# DMXDebugger.net
KiCad netlist of a schematic drawn in EAGLE
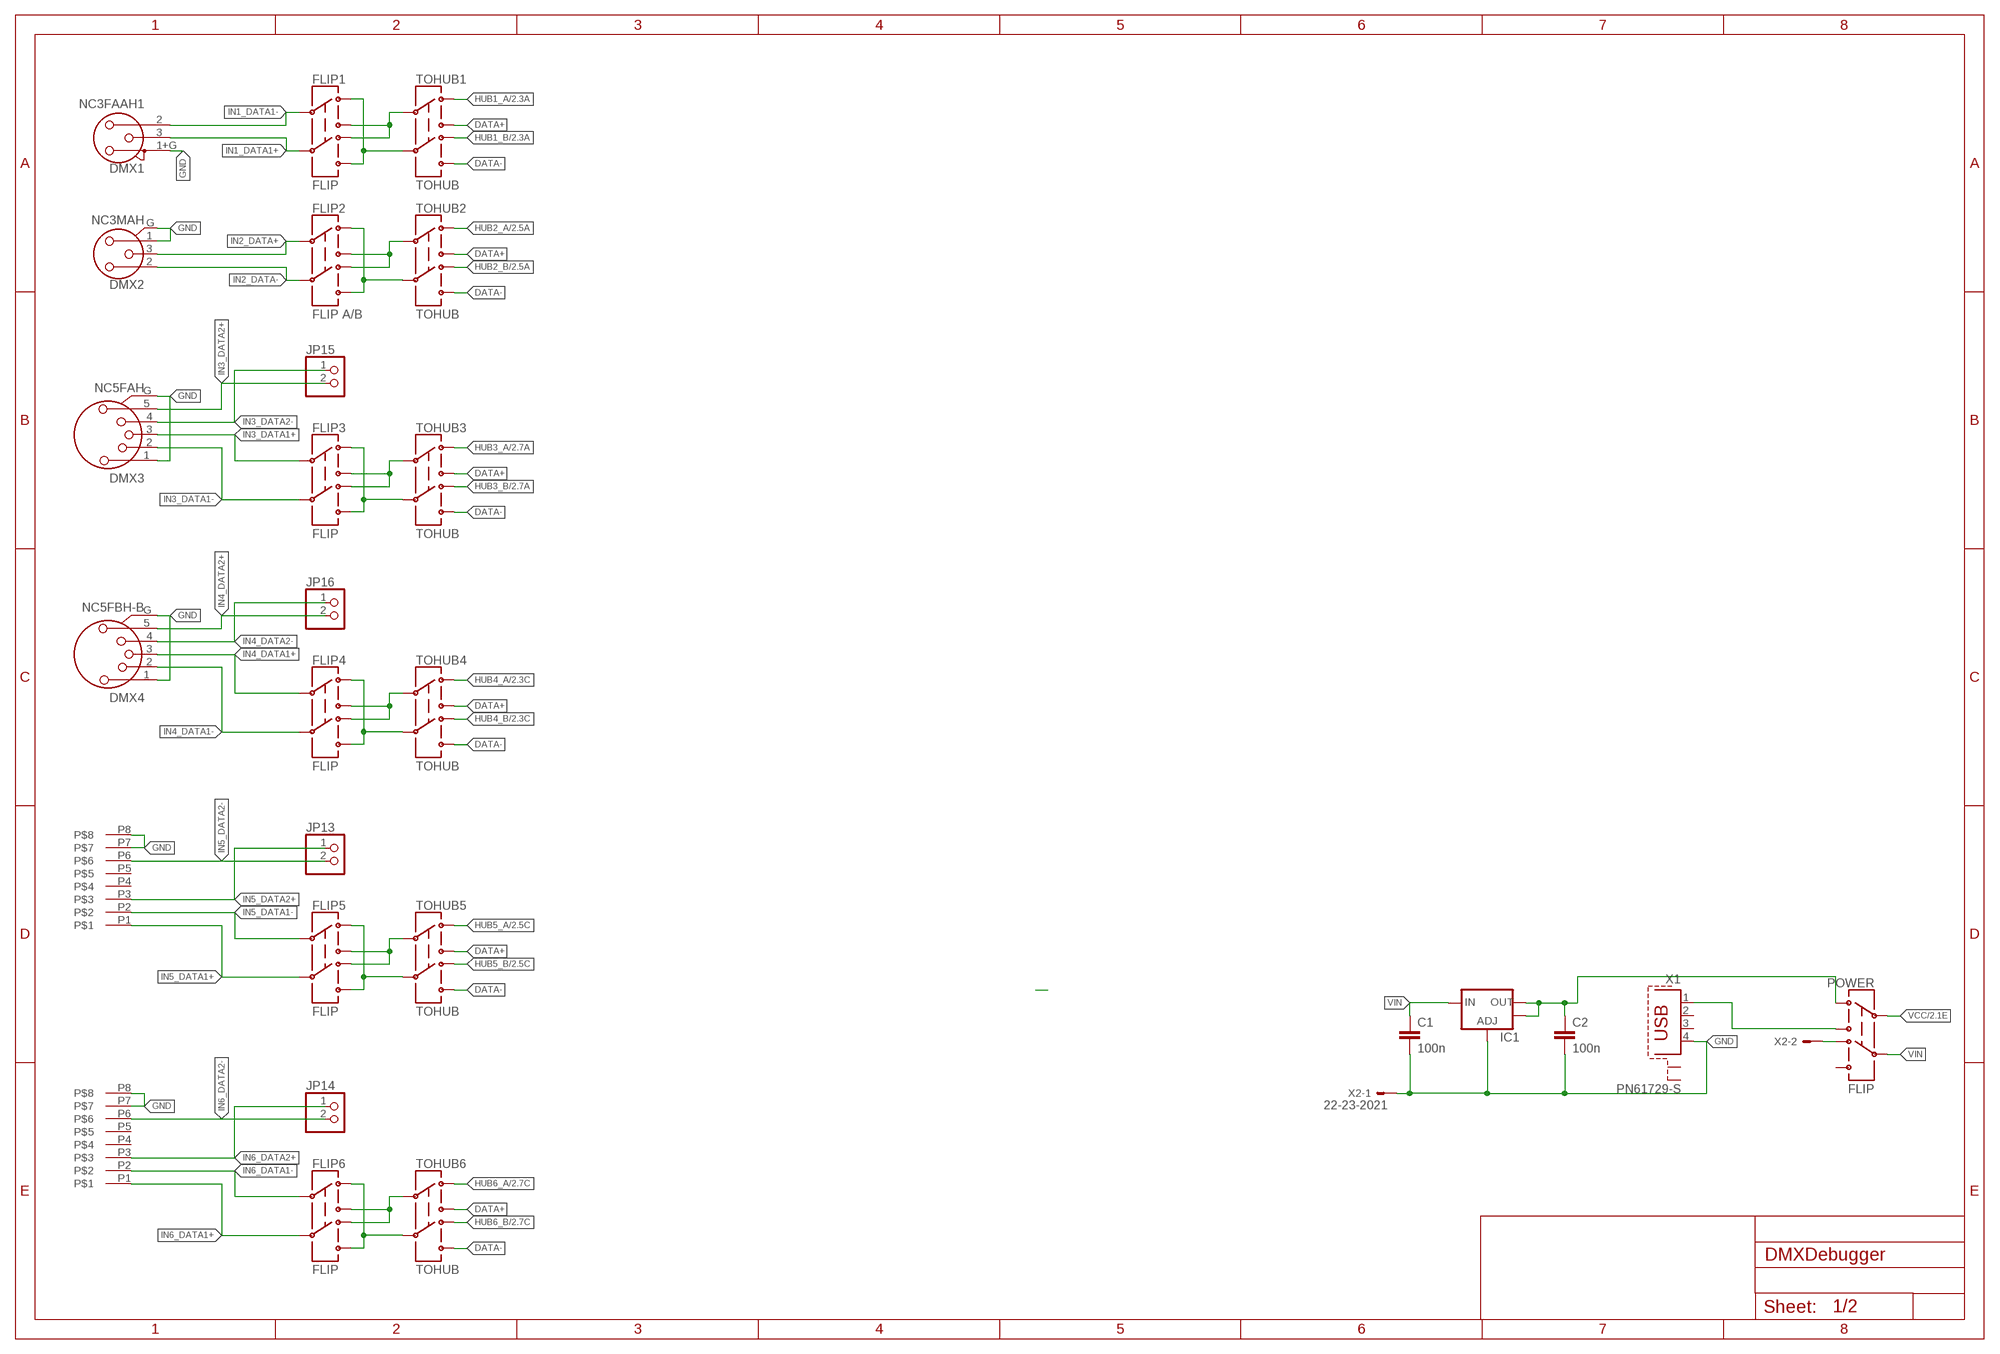
[diagram p0: schematic, sheet 1]
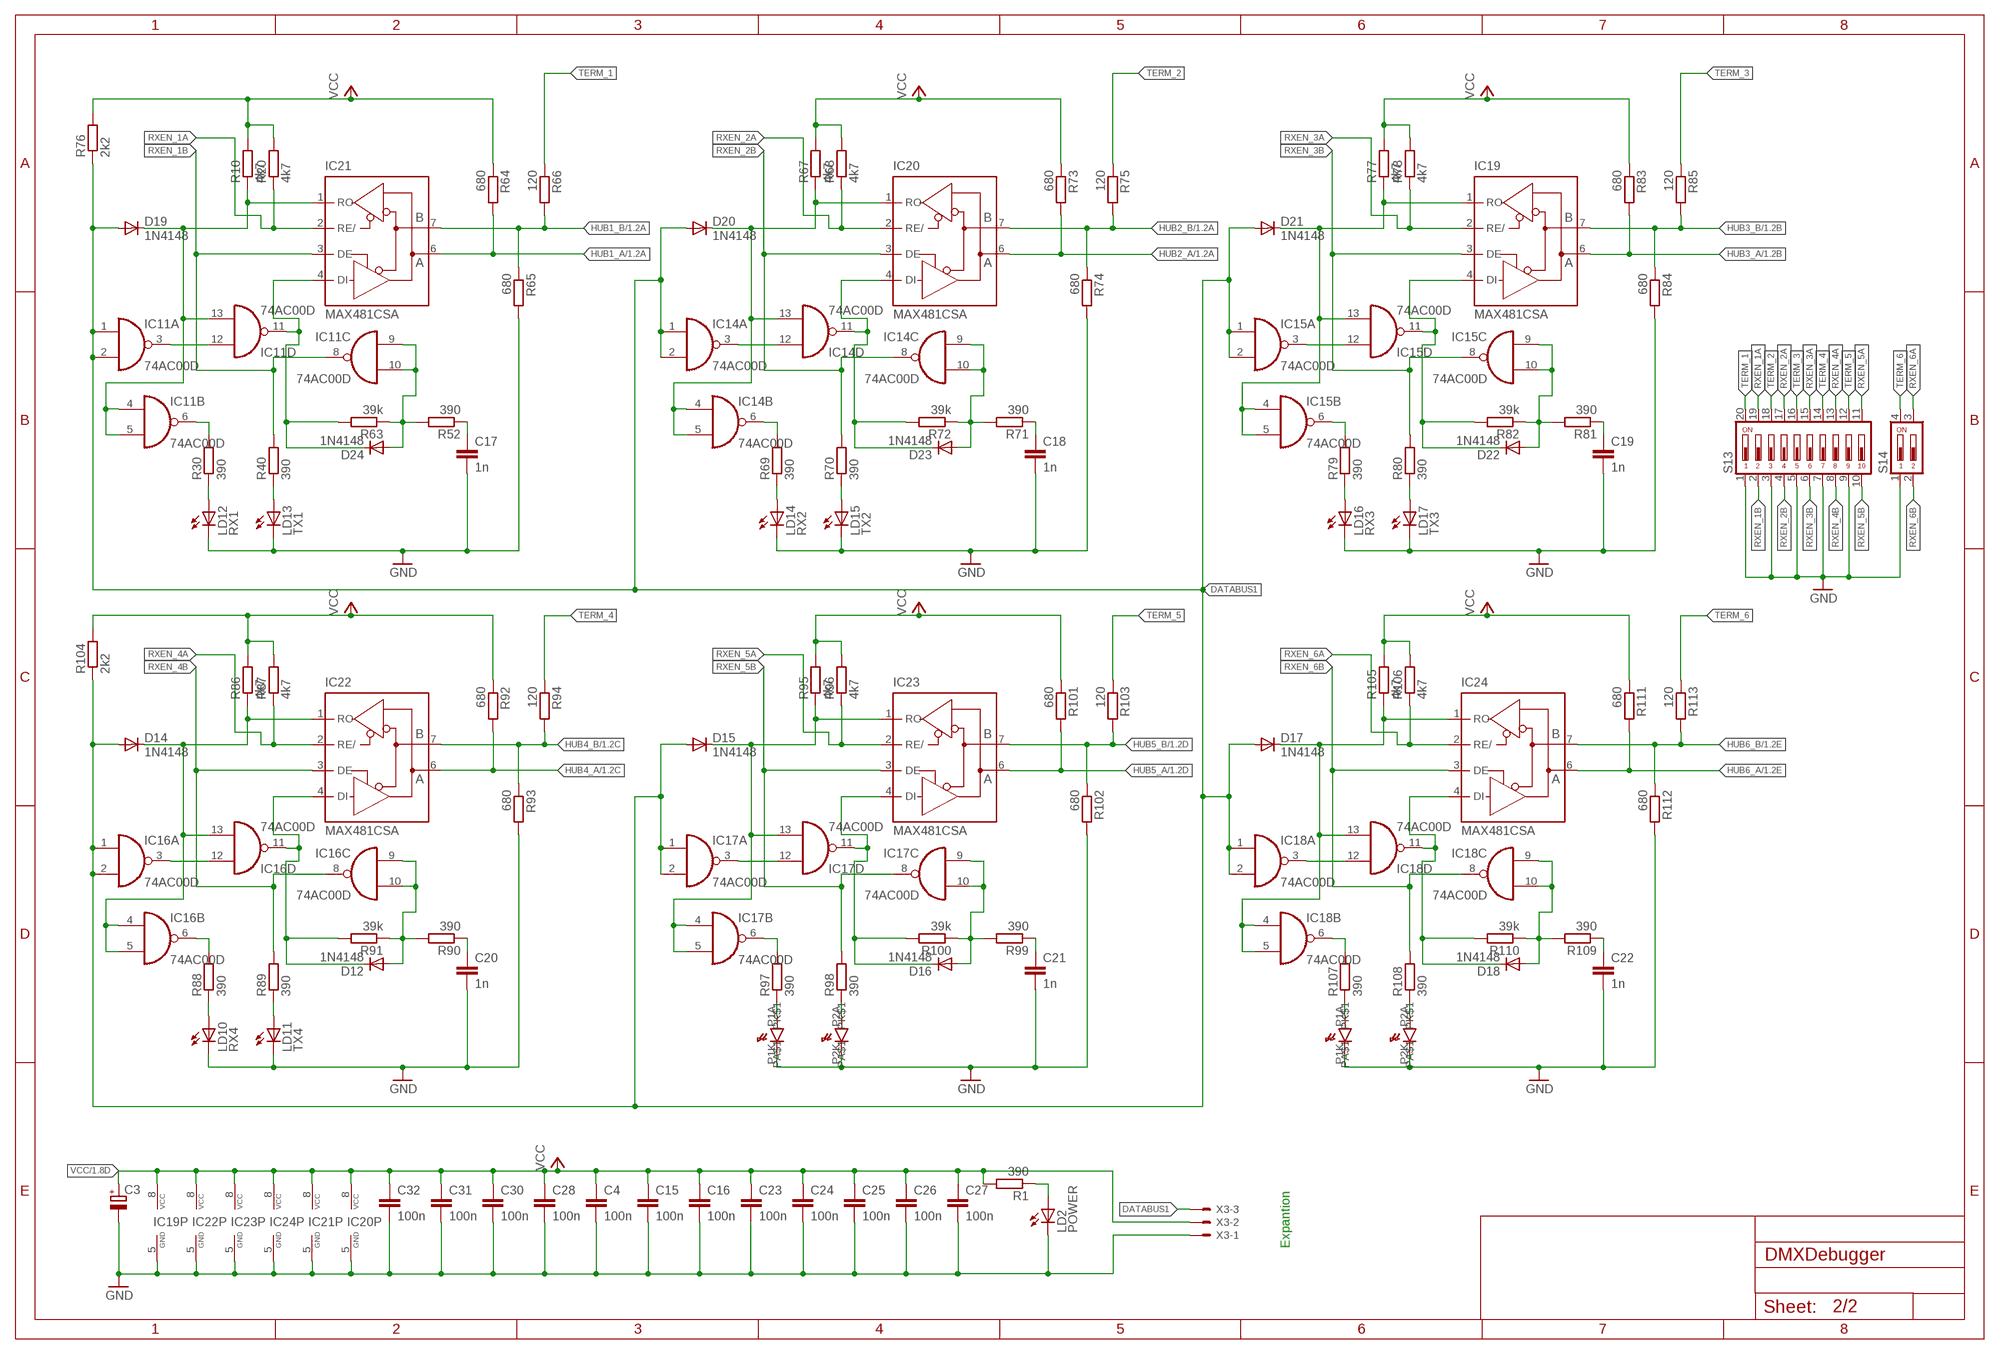
[diagram p1: schematic, sheet 2]

(export (version "E")
  (design (tool "Eeschema 10.0.6"))
  (components
    (comp (ref "C3")
      (value "CPOL-EUD")
      (footprint "eagle-import:PANASONIC_D")
      (libsource (lib "eagle-import") (part "CPOL-EUD"))
    )
    (comp (ref "C4")
      (value "100n")
      (footprint "eagle-import:C1206")
      (libsource (lib "eagle-import") (part "C-EUC1206"))
    )
    (comp (ref "C15")
      (value "100n")
      (footprint "eagle-import:C1206")
      (libsource (lib "eagle-import") (part "C-EUC1206"))
    )
    (comp (ref "C16")
      (value "100n")
      (footprint "eagle-import:C1206")
      (libsource (lib "eagle-import") (part "C-EUC1206"))
    )
    (comp (ref "C17")
      (value "1n")
      (footprint "eagle-import:C1206")
      (libsource (lib "eagle-import") (part "C-EUC1206"))
    )
    (comp (ref "C18")
      (value "1n")
      (footprint "eagle-import:C1206")
      (libsource (lib "eagle-import") (part "C-EUC1206"))
    )
    (comp (ref "C19")
      (value "1n")
      (footprint "eagle-import:C1206")
      (libsource (lib "eagle-import") (part "C-EUC1206"))
    )
    (comp (ref "C20")
      (value "1n")
      (footprint "eagle-import:C1206")
      (libsource (lib "eagle-import") (part "C-EUC1206"))
    )
    (comp (ref "C21")
      (value "1n")
      (footprint "eagle-import:C1206")
      (libsource (lib "eagle-import") (part "C-EUC1206"))
    )
    (comp (ref "C22")
      (value "1n")
      (footprint "eagle-import:C1206")
      (libsource (lib "eagle-import") (part "C-EUC1206"))
    )
    (comp (ref "C23")
      (value "100n")
      (footprint "eagle-import:C1206")
      (libsource (lib "eagle-import") (part "C-EUC1206"))
    )
    (comp (ref "C24")
      (value "100n")
      (footprint "eagle-import:C1206")
      (libsource (lib "eagle-import") (part "C-EUC1206"))
    )
    (comp (ref "C25")
      (value "100n")
      (footprint "eagle-import:C1206")
      (libsource (lib "eagle-import") (part "C-EUC1206"))
    )
    (comp (ref "C26")
      (value "100n")
      (footprint "eagle-import:C1206")
      (libsource (lib "eagle-import") (part "C-EUC1206"))
    )
    (comp (ref "C27")
      (value "100n")
      (footprint "eagle-import:C1206")
      (libsource (lib "eagle-import") (part "C-EUC1206"))
    )
    (comp (ref "C28")
      (value "100n")
      (footprint "eagle-import:C1206")
      (libsource (lib "eagle-import") (part "C-EUC1206"))
    )
    (comp (ref "C30")
      (value "100n")
      (footprint "eagle-import:C1206")
      (libsource (lib "eagle-import") (part "C-EUC1206"))
    )
    (comp (ref "C31")
      (value "100n")
      (footprint "eagle-import:C1206")
      (libsource (lib "eagle-import") (part "C-EUC1206"))
    )
    (comp (ref "C32")
      (value "100n")
      (footprint "eagle-import:C1206")
      (libsource (lib "eagle-import") (part "C-EUC1206"))
    )
    (comp (ref "D12")
      (value "1N4148")
      (footprint "eagle-import:MINIMELF")
      (libsource (lib "eagle-import") (part "DIODE-MINIMELF"))
    )
    (comp (ref "D14")
      (value "1N4148")
      (footprint "eagle-import:MINIMELF")
      (libsource (lib "eagle-import") (part "DIODE-MINIMELF"))
    )
    (comp (ref "D15")
      (value "1N4148")
      (footprint "eagle-import:MINIMELF")
      (libsource (lib "eagle-import") (part "DIODE-MINIMELF"))
    )
    (comp (ref "D16")
      (value "1N4148")
      (footprint "eagle-import:MINIMELF")
      (libsource (lib "eagle-import") (part "DIODE-MINIMELF"))
    )
    (comp (ref "D17")
      (value "1N4148")
      (footprint "eagle-import:MINIMELF")
      (libsource (lib "eagle-import") (part "DIODE-MINIMELF"))
    )
    (comp (ref "D18")
      (value "1N4148")
      (footprint "eagle-import:MINIMELF")
      (libsource (lib "eagle-import") (part "DIODE-MINIMELF"))
    )
    (comp (ref "D19")
      (value "1N4148")
      (footprint "eagle-import:MINIMELF")
      (libsource (lib "eagle-import") (part "DIODE-MINIMELF"))
    )
    (comp (ref "D20")
      (value "1N4148")
      (footprint "eagle-import:MINIMELF")
      (libsource (lib "eagle-import") (part "DIODE-MINIMELF"))
    )
    (comp (ref "D21")
      (value "1N4148")
      (footprint "eagle-import:MINIMELF")
      (libsource (lib "eagle-import") (part "DIODE-MINIMELF"))
    )
    (comp (ref "D22")
      (value "1N4148")
      (footprint "eagle-import:MINIMELF")
      (libsource (lib "eagle-import") (part "DIODE-MINIMELF"))
    )
    (comp (ref "D23")
      (value "1N4148")
      (footprint "eagle-import:MINIMELF")
      (libsource (lib "eagle-import") (part "DIODE-MINIMELF"))
    )
    (comp (ref "D24")
      (value "1N4148")
      (footprint "eagle-import:MINIMELF")
      (libsource (lib "eagle-import") (part "DIODE-MINIMELF"))
    )
    (comp (ref "DMX5")
      (value "RJHS508")
      (footprint "eagle-import:P-RJHS-538X")
      (libsource (lib "eagle-import") (part "RJHS508"))
    )
    (comp (ref "DMX6")
      (value "RJHS508")
      (footprint "eagle-import:P-RJHS-538X")
      (libsource (lib "eagle-import") (part "RJHS508"))
    )
    (comp (ref "IC11")
      (value "74AC00D")
      (footprint "eagle-import:SO14")
      (libsource (lib "eagle-import") (part "7400DAC"))
    )
    (comp (ref "IC14")
      (value "74AC00D")
      (footprint "eagle-import:SO14")
      (libsource (lib "eagle-import") (part "7400DAC"))
    )
    (comp (ref "IC15")
      (value "74AC00D")
      (footprint "eagle-import:SO14")
      (libsource (lib "eagle-import") (part "7400DAC"))
    )
    (comp (ref "IC16")
      (value "74AC00D")
      (footprint "eagle-import:SO14")
      (libsource (lib "eagle-import") (part "7400DAC"))
    )
    (comp (ref "IC17")
      (value "74AC00D")
      (footprint "eagle-import:SO14")
      (libsource (lib "eagle-import") (part "7400DAC"))
    )
    (comp (ref "IC18")
      (value "74AC00D")
      (footprint "eagle-import:SO14")
      (libsource (lib "eagle-import") (part "7400DAC"))
    )
    (comp (ref "IC19")
      (value "MAX481CSA")
      (footprint "eagle-import:SO08")
      (fields (field (name "MF") "MAXIM"))
      (libsource (lib "eagle-import") (part "MAX481CSA"))
    )
    (comp (ref "IC20")
      (value "MAX481CSA")
      (footprint "eagle-import:SO08")
      (fields (field (name "MF") "MAXIM"))
      (libsource (lib "eagle-import") (part "MAX481CSA"))
    )
    (comp (ref "IC21")
      (value "MAX481CSA")
      (footprint "eagle-import:SO08")
      (fields (field (name "MF") "MAXIM"))
      (libsource (lib "eagle-import") (part "MAX481CSA"))
    )
    (comp (ref "IC22")
      (value "MAX481CSA")
      (footprint "eagle-import:SO08")
      (fields (field (name "MF") "MAXIM"))
      (libsource (lib "eagle-import") (part "MAX481CSA"))
    )
    (comp (ref "IC23")
      (value "MAX481CSA")
      (footprint "eagle-import:SO08")
      (fields (field (name "MF") "MAXIM"))
      (libsource (lib "eagle-import") (part "MAX481CSA"))
    )
    (comp (ref "IC24")
      (value "MAX481CSA")
      (footprint "eagle-import:SO08")
      (fields (field (name "MF") "MAXIM"))
      (libsource (lib "eagle-import") (part "MAX481CSA"))
    )
    (comp (ref "LD2")
      (value "POWER")
      (footprint "eagle-import:CHIP-LED0603")
      (libsource (lib "eagle-import") (part "LEDCHIP-LED0603"))
    )
    (comp (ref "LD10")
      (value "RX4")
      (footprint "eagle-import:CHIP-LED0603")
      (libsource (lib "eagle-import") (part "LEDCHIP-LED0603"))
    )
    (comp (ref "LD11")
      (value "TX4")
      (footprint "eagle-import:CHIP-LED0603")
      (libsource (lib "eagle-import") (part "LEDCHIP-LED0603"))
    )
    (comp (ref "LD12")
      (value "RX1")
      (footprint "eagle-import:CHIP-LED0603")
      (libsource (lib "eagle-import") (part "LEDCHIP-LED0603"))
    )
    (comp (ref "LD13")
      (value "TX1")
      (footprint "eagle-import:CHIP-LED0603")
      (libsource (lib "eagle-import") (part "LEDCHIP-LED0603"))
    )
    (comp (ref "LD14")
      (value "RX2")
      (footprint "eagle-import:CHIP-LED0603")
      (libsource (lib "eagle-import") (part "LEDCHIP-LED0603"))
    )
    (comp (ref "LD15")
      (value "TX2")
      (footprint "eagle-import:CHIP-LED0603")
      (libsource (lib "eagle-import") (part "LEDCHIP-LED0603"))
    )
    (comp (ref "LD16")
      (value "RX3")
      (footprint "eagle-import:CHIP-LED0603")
      (libsource (lib "eagle-import") (part "LEDCHIP-LED0603"))
    )
    (comp (ref "LD17")
      (value "TX3")
      (footprint "eagle-import:CHIP-LED0603")
      (libsource (lib "eagle-import") (part "LEDCHIP-LED0603"))
    )
    (comp (ref "R1")
      (value "390")
      (footprint "eagle-import:R1206")
      (libsource (lib "eagle-import") (part "R-EU_R1206"))
    )
    (comp (ref "R10")
      (value "4k7")
      (footprint "eagle-import:R1206")
      (libsource (lib "eagle-import") (part "R-EU_R1206"))
    )
    (comp (ref "R20")
      (value "4k7")
      (footprint "eagle-import:R1206")
      (libsource (lib "eagle-import") (part "R-EU_R1206"))
    )
    (comp (ref "R30")
      (value "390")
      (footprint "eagle-import:R1206")
      (libsource (lib "eagle-import") (part "R-EU_R1206"))
    )
    (comp (ref "R40")
      (value "390")
      (footprint "eagle-import:R1206")
      (libsource (lib "eagle-import") (part "R-EU_R1206"))
    )
    (comp (ref "R52")
      (value "390")
      (footprint "eagle-import:R1206")
      (libsource (lib "eagle-import") (part "R-EU_R1206"))
    )
    (comp (ref "R63")
      (value "39k")
      (footprint "eagle-import:R1206")
      (libsource (lib "eagle-import") (part "R-EU_R1206"))
    )
    (comp (ref "R64")
      (value "680")
      (footprint "eagle-import:R1206")
      (libsource (lib "eagle-import") (part "R-EU_R1206"))
    )
    (comp (ref "R65")
      (value "680")
      (footprint "eagle-import:R1206")
      (libsource (lib "eagle-import") (part "R-EU_R1206"))
    )
    (comp (ref "R66")
      (value "120")
      (footprint "eagle-import:R1206")
      (libsource (lib "eagle-import") (part "R-EU_R1206"))
    )
    (comp (ref "R67")
      (value "4k7")
      (footprint "eagle-import:R1206")
      (libsource (lib "eagle-import") (part "R-EU_R1206"))
    )
    (comp (ref "R68")
      (value "4k7")
      (footprint "eagle-import:R1206")
      (libsource (lib "eagle-import") (part "R-EU_R1206"))
    )
    (comp (ref "R69")
      (value "390")
      (footprint "eagle-import:R1206")
      (libsource (lib "eagle-import") (part "R-EU_R1206"))
    )
    (comp (ref "R70")
      (value "390")
      (footprint "eagle-import:R1206")
      (libsource (lib "eagle-import") (part "R-EU_R1206"))
    )
    (comp (ref "R71")
      (value "390")
      (footprint "eagle-import:R1206")
      (libsource (lib "eagle-import") (part "R-EU_R1206"))
    )
    (comp (ref "R72")
      (value "39k")
      (footprint "eagle-import:R1206")
      (libsource (lib "eagle-import") (part "R-EU_R1206"))
    )
    (comp (ref "R73")
      (value "680")
      (footprint "eagle-import:R1206")
      (libsource (lib "eagle-import") (part "R-EU_R1206"))
    )
    (comp (ref "R74")
      (value "680")
      (footprint "eagle-import:R1206")
      (libsource (lib "eagle-import") (part "R-EU_R1206"))
    )
    (comp (ref "R75")
      (value "120")
      (footprint "eagle-import:R1206")
      (libsource (lib "eagle-import") (part "R-EU_R1206"))
    )
    (comp (ref "R76")
      (value "2k2")
      (footprint "eagle-import:R1206")
      (libsource (lib "eagle-import") (part "R-EU_R1206"))
    )
    (comp (ref "R77")
      (value "4k7")
      (footprint "eagle-import:R1206")
      (libsource (lib "eagle-import") (part "R-EU_R1206"))
    )
    (comp (ref "R78")
      (value "4k7")
      (footprint "eagle-import:R1206")
      (libsource (lib "eagle-import") (part "R-EU_R1206"))
    )
    (comp (ref "R79")
      (value "390")
      (footprint "eagle-import:R1206")
      (libsource (lib "eagle-import") (part "R-EU_R1206"))
    )
    (comp (ref "R80")
      (value "390")
      (footprint "eagle-import:R1206")
      (libsource (lib "eagle-import") (part "R-EU_R1206"))
    )
    (comp (ref "R81")
      (value "390")
      (footprint "eagle-import:R1206")
      (libsource (lib "eagle-import") (part "R-EU_R1206"))
    )
    (comp (ref "R82")
      (value "39k")
      (footprint "eagle-import:R1206")
      (libsource (lib "eagle-import") (part "R-EU_R1206"))
    )
    (comp (ref "R83")
      (value "680")
      (footprint "eagle-import:R1206")
      (libsource (lib "eagle-import") (part "R-EU_R1206"))
    )
    (comp (ref "R84")
      (value "680")
      (footprint "eagle-import:R1206")
      (libsource (lib "eagle-import") (part "R-EU_R1206"))
    )
    (comp (ref "R85")
      (value "120")
      (footprint "eagle-import:R1206")
      (libsource (lib "eagle-import") (part "R-EU_R1206"))
    )
    (comp (ref "R86")
      (value "4k7")
      (footprint "eagle-import:R1206")
      (libsource (lib "eagle-import") (part "R-EU_R1206"))
    )
    (comp (ref "R87")
      (value "4k7")
      (footprint "eagle-import:R1206")
      (libsource (lib "eagle-import") (part "R-EU_R1206"))
    )
    (comp (ref "R88")
      (value "390")
      (footprint "eagle-import:R1206")
      (libsource (lib "eagle-import") (part "R-EU_R1206"))
    )
    (comp (ref "R89")
      (value "390")
      (footprint "eagle-import:R1206")
      (libsource (lib "eagle-import") (part "R-EU_R1206"))
    )
    (comp (ref "R90")
      (value "390")
      (footprint "eagle-import:R1206")
      (libsource (lib "eagle-import") (part "R-EU_R1206"))
    )
    (comp (ref "R91")
      (value "39k")
      (footprint "eagle-import:R1206")
      (libsource (lib "eagle-import") (part "R-EU_R1206"))
    )
    (comp (ref "R92")
      (value "680")
      (footprint "eagle-import:R1206")
      (libsource (lib "eagle-import") (part "R-EU_R1206"))
    )
    (comp (ref "R93")
      (value "680")
      (footprint "eagle-import:R1206")
      (libsource (lib "eagle-import") (part "R-EU_R1206"))
    )
    (comp (ref "R94")
      (value "120")
      (footprint "eagle-import:R1206")
      (libsource (lib "eagle-import") (part "R-EU_R1206"))
    )
    (comp (ref "R95")
      (value "4k7")
      (footprint "eagle-import:R1206")
      (libsource (lib "eagle-import") (part "R-EU_R1206"))
    )
    (comp (ref "R96")
      (value "4k7")
      (footprint "eagle-import:R1206")
      (libsource (lib "eagle-import") (part "R-EU_R1206"))
    )
    (comp (ref "R97")
      (value "390")
      (footprint "eagle-import:R1206")
      (libsource (lib "eagle-import") (part "R-EU_R1206"))
    )
    (comp (ref "R98")
      (value "390")
      (footprint "eagle-import:R1206")
      (libsource (lib "eagle-import") (part "R-EU_R1206"))
    )
    (comp (ref "R99")
      (value "390")
      (footprint "eagle-import:R1206")
      (libsource (lib "eagle-import") (part "R-EU_R1206"))
    )
    (comp (ref "R100")
      (value "39k")
      (footprint "eagle-import:R1206")
      (libsource (lib "eagle-import") (part "R-EU_R1206"))
    )
    (comp (ref "R101")
      (value "680")
      (footprint "eagle-import:R1206")
      (libsource (lib "eagle-import") (part "R-EU_R1206"))
    )
    (comp (ref "R102")
      (value "680")
      (footprint "eagle-import:R1206")
      (libsource (lib "eagle-import") (part "R-EU_R1206"))
    )
    (comp (ref "R103")
      (value "120")
      (footprint "eagle-import:R1206")
      (libsource (lib "eagle-import") (part "R-EU_R1206"))
    )
    (comp (ref "R104")
      (value "2k2")
      (footprint "eagle-import:R1206")
      (libsource (lib "eagle-import") (part "R-EU_R1206"))
    )
    (comp (ref "R105")
      (value "4k7")
      (footprint "eagle-import:R1206")
      (libsource (lib "eagle-import") (part "R-EU_R1206"))
    )
    (comp (ref "R106")
      (value "4k7")
      (footprint "eagle-import:R1206")
      (libsource (lib "eagle-import") (part "R-EU_R1206"))
    )
    (comp (ref "R107")
      (value "390")
      (footprint "eagle-import:R1206")
      (libsource (lib "eagle-import") (part "R-EU_R1206"))
    )
    (comp (ref "R108")
      (value "390")
      (footprint "eagle-import:R1206")
      (libsource (lib "eagle-import") (part "R-EU_R1206"))
    )
    (comp (ref "R109")
      (value "390")
      (footprint "eagle-import:R1206")
      (libsource (lib "eagle-import") (part "R-EU_R1206"))
    )
    (comp (ref "R110")
      (value "39k")
      (footprint "eagle-import:R1206")
      (libsource (lib "eagle-import") (part "R-EU_R1206"))
    )
    (comp (ref "R111")
      (value "680")
      (footprint "eagle-import:R1206")
      (libsource (lib "eagle-import") (part "R-EU_R1206"))
    )
    (comp (ref "R112")
      (value "680")
      (footprint "eagle-import:R1206")
      (libsource (lib "eagle-import") (part "R-EU_R1206"))
    )
    (comp (ref "R113")
      (value "120")
      (footprint "eagle-import:R1206")
      (libsource (lib "eagle-import") (part "R-EU_R1206"))
    )
    (comp (ref "S13")
      (value "DIP10YL")
      (footprint "eagle-import:DIP10YL")
      (libsource (lib "eagle-import") (part "DIP10YL"))
    )
    (comp (ref "S14")
      (value "DIP02YL")
      (footprint "eagle-import:DIP02YL")
      (libsource (lib "eagle-import") (part "DIP02YL"))
    )
    (comp (ref "X3")
      (value "22-23-2031")
      (footprint "eagle-import:22-23-2031")
      (fields (field (name "MF") "MOLEX"))
      (libsource (lib "eagle-import") (part "22-23-2031"))
    )
    (comp (ref "C1")
      (value "100n")
      (footprint "eagle-import:C1206")
      (libsource (lib "eagle-import") (part "C-EUC1206"))
    )
    (comp (ref "C2")
      (value "100n")
      (footprint "eagle-import:C1206")
      (libsource (lib "eagle-import") (part "C-EUC1206"))
    )
    (comp (ref "DMX1")
      (value "NC3FAAH1")
      (footprint "eagle-import:NC3FAH1")
      (fields (field (name "OC_FARNELL") "1310019"))
      (libsource (lib "eagle-import") (part "MC3?FAH1"))
    )
    (comp (ref "DMX2")
      (value "NC3MAH")
      (footprint "eagle-import:NC3FAH2")
      (fields (field (name "MPN") "NC3FAH2") (field (name "OC_FARNELL") "724543"))
      (libsource (lib "eagle-import") (part "NC3FAH2"))
    )
    (comp (ref "DMX3")
      (value "NC5FAH")
      (footprint "eagle-import:NC5FAH")
      (fields (field (name "MF") "FARNELL"))
      (libsource (lib "eagle-import") (part "NC5FAH"))
    )
    (comp (ref "DMX4")
      (value "NC5FBH-B")
      (footprint "eagle-import:NC5FBH-B")
      (libsource (lib "eagle-import") (part "NC5FBH-B"))
    )
    (comp (ref "FLIP1")
      (value "FLIP")
      (footprint "eagle-import:MSS-2235")
      (libsource (lib "eagle-import") (part "SWITCH-DPDT"))
    )
    (comp (ref "FLIP2")
      (value "FLIP A/B")
      (footprint "eagle-import:MSS-2235")
      (libsource (lib "eagle-import") (part "SWITCH-DPDT"))
    )
    (comp (ref "FLIP3")
      (value "FLIP")
      (footprint "eagle-import:MSS-2235")
      (libsource (lib "eagle-import") (part "SWITCH-DPDT"))
    )
    (comp (ref "FLIP4")
      (value "FLIP")
      (footprint "eagle-import:MSS-2235")
      (libsource (lib "eagle-import") (part "SWITCH-DPDT"))
    )
    (comp (ref "FLIP5")
      (value "FLIP")
      (footprint "eagle-import:MSS-2235")
      (libsource (lib "eagle-import") (part "SWITCH-DPDT"))
    )
    (comp (ref "FLIP6")
      (value "FLIP")
      (footprint "eagle-import:MSS-2235")
      (libsource (lib "eagle-import") (part "SWITCH-DPDT"))
    )
    (comp (ref "IC1")
      (value "V_REG_LM1117SOT223")
      (footprint "eagle-import:SOT223")
      (libsource (lib "eagle-import") (part "V_REG_LM1117SOT223"))
    )
    (comp (ref "JP13")
      (value "PINHD-1X2")
      (footprint "eagle-import:1X02")
      (libsource (lib "eagle-import") (part "PINHD-1X2"))
    )
    (comp (ref "JP14")
      (value "PINHD-1X2")
      (footprint "eagle-import:1X02")
      (libsource (lib "eagle-import") (part "PINHD-1X2"))
    )
    (comp (ref "JP15")
      (value "PINHD-1X2")
      (footprint "eagle-import:1X02")
      (libsource (lib "eagle-import") (part "PINHD-1X2"))
    )
    (comp (ref "JP16")
      (value "PINHD-1X2")
      (footprint "eagle-import:1X02")
      (libsource (lib "eagle-import") (part "PINHD-1X2"))
    )
    (comp (ref "POWER")
      (value "FLIP")
      (footprint "eagle-import:MSS-2235")
      (libsource (lib "eagle-import") (part "SWITCH-DPDT"))
    )
    (comp (ref "TOHUB1")
      (value "TOHUB")
      (footprint "eagle-import:MSS-2235")
      (libsource (lib "eagle-import") (part "SWITCH-DPDT"))
    )
    (comp (ref "TOHUB2")
      (value "TOHUB")
      (footprint "eagle-import:MSS-2235")
      (libsource (lib "eagle-import") (part "SWITCH-DPDT"))
    )
    (comp (ref "TOHUB3")
      (value "TOHUB")
      (footprint "eagle-import:MSS-2235")
      (libsource (lib "eagle-import") (part "SWITCH-DPDT"))
    )
    (comp (ref "TOHUB4")
      (value "TOHUB")
      (footprint "eagle-import:MSS-2235")
      (libsource (lib "eagle-import") (part "SWITCH-DPDT"))
    )
    (comp (ref "TOHUB5")
      (value "TOHUB")
      (footprint "eagle-import:MSS-2235")
      (libsource (lib "eagle-import") (part "SWITCH-DPDT"))
    )
    (comp (ref "TOHUB6")
      (value "TOHUB")
      (footprint "eagle-import:MSS-2235")
      (libsource (lib "eagle-import") (part "SWITCH-DPDT"))
    )
    (comp (ref "X1")
      (value "PN61729-S")
      (footprint "eagle-import:PN61729-S")
      (libsource (lib "eagle-import") (part "PN61729-S"))
    )
    (comp (ref "X2")
      (value "22-23-2021")
      (footprint "eagle-import:22-23-2021")
      (fields (field (name "MF") "MOLEX"))
      (libsource (lib "eagle-import") (part "22-23-2021"))
    )
  )
  (nets
    (net (code "1") (name "DATA+") (class "Default")
      (node (ref "TOHUB1") (pin "3") (pinfunction "3_3") (pintype "bidirectional"))
      (node (ref "TOHUB2") (pin "3") (pinfunction "3_3") (pintype "bidirectional"))
      (node (ref "TOHUB3") (pin "3") (pinfunction "3_3") (pintype "bidirectional"))
      (node (ref "TOHUB4") (pin "3") (pinfunction "3_3") (pintype "bidirectional"))
      (node (ref "TOHUB5") (pin "3") (pinfunction "3_3") (pintype "bidirectional"))
      (node (ref "TOHUB6") (pin "3") (pinfunction "3_3") (pintype "bidirectional"))
    )
    (net (code "2") (name "DATA-") (class "Default")
      (node (ref "TOHUB1") (pin "4") (pinfunction "6_4") (pintype "bidirectional"))
      (node (ref "TOHUB2") (pin "4") (pinfunction "6_4") (pintype "bidirectional"))
      (node (ref "TOHUB3") (pin "4") (pinfunction "6_4") (pintype "bidirectional"))
      (node (ref "TOHUB4") (pin "4") (pinfunction "6_4") (pintype "bidirectional"))
      (node (ref "TOHUB5") (pin "4") (pinfunction "6_4") (pintype "bidirectional"))
      (node (ref "TOHUB6") (pin "4") (pinfunction "6_4") (pintype "bidirectional"))
    )
    (net (code "3") (name "DATABUS1") (class "Default")
      (node (ref "D14") (pin "A") (pinfunction "A_A") (pintype "passive"))
      (node (ref "D15") (pin "A") (pinfunction "A_A") (pintype "passive"))
      (node (ref "D17") (pin "A") (pinfunction "A_A") (pintype "passive"))
      (node (ref "D19") (pin "A") (pinfunction "A_A") (pintype "passive"))
      (node (ref "D20") (pin "A") (pinfunction "A_A") (pintype "passive"))
      (node (ref "D21") (pin "A") (pinfunction "A_A") (pintype "passive"))
      (node (ref "IC11") (pin "1") (pinfunction "I0_1") (pintype "input"))
      (node (ref "IC11") (pin "2") (pinfunction "I1_2") (pintype "input"))
      (node (ref "IC14") (pin "1") (pinfunction "I0_1") (pintype "input"))
      (node (ref "IC14") (pin "2") (pinfunction "I1_2") (pintype "input"))
      (node (ref "IC15") (pin "1") (pinfunction "I0_1") (pintype "input"))
      (node (ref "IC15") (pin "2") (pinfunction "I1_2") (pintype "input"))
      (node (ref "IC16") (pin "1") (pinfunction "I0_1") (pintype "input"))
      (node (ref "IC16") (pin "2") (pinfunction "I1_2") (pintype "input"))
      (node (ref "IC17") (pin "1") (pinfunction "I0_1") (pintype "input"))
      (node (ref "IC17") (pin "2") (pinfunction "I1_2") (pintype "input"))
      (node (ref "IC18") (pin "1") (pinfunction "I0_1") (pintype "input"))
      (node (ref "IC18") (pin "2") (pinfunction "I1_2") (pintype "input"))
      (node (ref "R104") (pin "1") (pinfunction "1_1") (pintype "passive"))
      (node (ref "R76") (pin "1") (pinfunction "1_1") (pintype "passive"))
      (node (ref "X3") (pin "3") (pinfunction "S_3") (pintype "passive"))
    )
    (net (code "4") (name "GND") (class "Default")
      (node (ref "C1") (pin "2") (pinfunction "2_2") (pintype "passive"))
      (node (ref "C15") (pin "2") (pinfunction "2_2") (pintype "passive"))
      (node (ref "C16") (pin "2") (pinfunction "2_2") (pintype "passive"))
      (node (ref "C17") (pin "2") (pinfunction "2_2") (pintype "passive"))
      (node (ref "C18") (pin "2") (pinfunction "2_2") (pintype "passive"))
      (node (ref "C19") (pin "2") (pinfunction "2_2") (pintype "passive"))
      (node (ref "C2") (pin "2") (pinfunction "2_2") (pintype "passive"))
      (node (ref "C20") (pin "2") (pinfunction "2_2") (pintype "passive"))
      (node (ref "C21") (pin "2") (pinfunction "2_2") (pintype "passive"))
      (node (ref "C22") (pin "2") (pinfunction "2_2") (pintype "passive"))
      (node (ref "C23") (pin "2") (pinfunction "2_2") (pintype "passive"))
      (node (ref "C24") (pin "2") (pinfunction "2_2") (pintype "passive"))
      (node (ref "C25") (pin "2") (pinfunction "2_2") (pintype "passive"))
      (node (ref "C26") (pin "2") (pinfunction "2_2") (pintype "passive"))
      (node (ref "C27") (pin "2") (pinfunction "2_2") (pintype "passive"))
      (node (ref "C28") (pin "2") (pinfunction "2_2") (pintype "passive"))
      (node (ref "C3") (pin "-") (pinfunction "-_-") (pintype "passive"))
      (node (ref "C30") (pin "2") (pinfunction "2_2") (pintype "passive"))
      (node (ref "C31") (pin "2") (pinfunction "2_2") (pintype "passive"))
      (node (ref "C32") (pin "2") (pinfunction "2_2") (pintype "passive"))
      (node (ref "C4") (pin "2") (pinfunction "2_2") (pintype "passive"))
      (node (ref "DMX1") (pin "1+G") (pinfunction "1_1+G") (pintype "passive"))
      (node (ref "DMX2") (pin "1") (pinfunction "2_1") (pintype "passive"))
      (node (ref "DMX2") (pin "G") (pinfunction "G_G") (pintype "passive"))
      (node (ref "DMX3") (pin "1") (pinfunction "1_1") (pintype "passive"))
      (node (ref "DMX3") (pin "G") (pinfunction "G_G") (pintype "passive"))
      (node (ref "DMX4") (pin "1") (pinfunction "1_1") (pintype "passive"))
      (node (ref "DMX4") (pin "G") (pinfunction "G_G") (pintype "passive"))
      (node (ref "DMX5") (pin "P1K") (pinfunction "PK$1_P1K") (pintype "bidirectional"))
      (node (ref "DMX5") (pin "P2K") (pinfunction "PK$1_P2K") (pintype "bidirectional"))
      (node (ref "DMX5") (pin "P7") (pinfunction "P$7_P7") (pintype "bidirectional"))
      (node (ref "DMX5") (pin "P8") (pinfunction "P$8_P8") (pintype "bidirectional"))
      (node (ref "DMX6") (pin "P1K") (pinfunction "PK$1_P1K") (pintype "bidirectional"))
      (node (ref "DMX6") (pin "P2K") (pinfunction "PK$1_P2K") (pintype "bidirectional"))
      (node (ref "DMX6") (pin "P7") (pinfunction "P$7_P7") (pintype "bidirectional"))
      (node (ref "DMX6") (pin "P8") (pinfunction "P$8_P8") (pintype "bidirectional"))
      (node (ref "IC1") (pin "1") (pinfunction "ADJ_1") (pintype "input"))
      (node (ref "IC19") (pin "5") (pinfunction "GND_5") (pintype "power_in"))
      (node (ref "IC20") (pin "5") (pinfunction "GND_5") (pintype "power_in"))
      (node (ref "IC21") (pin "5") (pinfunction "GND_5") (pintype "power_in"))
      (node (ref "IC22") (pin "5") (pinfunction "GND_5") (pintype "power_in"))
      (node (ref "IC23") (pin "5") (pinfunction "GND_5") (pintype "power_in"))
      (node (ref "IC24") (pin "5") (pinfunction "GND_5") (pintype "power_in"))
      (node (ref "LD10") (pin "C") (pinfunction "C_C") (pintype "passive"))
      (node (ref "LD11") (pin "C") (pinfunction "C_C") (pintype "passive"))
      (node (ref "LD12") (pin "C") (pinfunction "C_C") (pintype "passive"))
      (node (ref "LD13") (pin "C") (pinfunction "C_C") (pintype "passive"))
      (node (ref "LD14") (pin "C") (pinfunction "C_C") (pintype "passive"))
      (node (ref "LD15") (pin "C") (pinfunction "C_C") (pintype "passive"))
      (node (ref "LD16") (pin "C") (pinfunction "C_C") (pintype "passive"))
      (node (ref "LD17") (pin "C") (pinfunction "C_C") (pintype "passive"))
      (node (ref "LD2") (pin "C") (pinfunction "C_C") (pintype "passive"))
      (node (ref "R102") (pin "2") (pinfunction "2_2") (pintype "passive"))
      (node (ref "R112") (pin "2") (pinfunction "2_2") (pintype "passive"))
      (node (ref "R65") (pin "2") (pinfunction "2_2") (pintype "passive"))
      (node (ref "R74") (pin "2") (pinfunction "2_2") (pintype "passive"))
      (node (ref "R84") (pin "2") (pinfunction "2_2") (pintype "passive"))
      (node (ref "R93") (pin "2") (pinfunction "2_2") (pintype "passive"))
      (node (ref "S13") (pin "1") (pinfunction "1_1") (pintype "passive"))
      (node (ref "S13") (pin "3") (pinfunction "3_3") (pintype "passive"))
      (node (ref "S13") (pin "5") (pinfunction "5_5") (pintype "passive"))
      (node (ref "S13") (pin "7") (pinfunction "7_7") (pintype "passive"))
      (node (ref "S13") (pin "9") (pinfunction "9_9") (pintype "passive"))
      (node (ref "S14") (pin "1") (pinfunction "1_1") (pintype "passive"))
      (node (ref "X1") (pin "4") (pinfunction "4_4") (pintype "passive"))
      (node (ref "X2") (pin "1") (pinfunction "S_1") (pintype "passive"))
      (node (ref "X3") (pin "1") (pinfunction "S_1") (pintype "passive"))
    )
    (net (code "5") (name "HUB1_A") (class "Default")
      (node (ref "IC21") (pin "6") (pinfunction "A_6") (pintype "passive"))
      (node (ref "R64") (pin "2") (pinfunction "2_2") (pintype "passive"))
      (node (ref "TOHUB1") (pin "1") (pinfunction "1_1") (pintype "bidirectional"))
    )
    (net (code "6") (name "HUB1_B") (class "Default")
      (node (ref "IC21") (pin "7") (pinfunction "B_7") (pintype "passive"))
      (node (ref "R65") (pin "1") (pinfunction "1_1") (pintype "passive"))
      (node (ref "R66") (pin "2") (pinfunction "2_2") (pintype "passive"))
      (node (ref "TOHUB1") (pin "6") (pinfunction "4_6") (pintype "bidirectional"))
    )
    (net (code "7") (name "HUB2_A") (class "Default")
      (node (ref "IC20") (pin "6") (pinfunction "A_6") (pintype "passive"))
      (node (ref "R73") (pin "2") (pinfunction "2_2") (pintype "passive"))
      (node (ref "TOHUB2") (pin "1") (pinfunction "1_1") (pintype "bidirectional"))
    )
    (net (code "8") (name "HUB2_B") (class "Default")
      (node (ref "IC20") (pin "7") (pinfunction "B_7") (pintype "passive"))
      (node (ref "R74") (pin "1") (pinfunction "1_1") (pintype "passive"))
      (node (ref "R75") (pin "2") (pinfunction "2_2") (pintype "passive"))
      (node (ref "TOHUB2") (pin "6") (pinfunction "4_6") (pintype "bidirectional"))
    )
    (net (code "9") (name "HUB3_A") (class "Default")
      (node (ref "IC19") (pin "6") (pinfunction "A_6") (pintype "passive"))
      (node (ref "R83") (pin "2") (pinfunction "2_2") (pintype "passive"))
      (node (ref "TOHUB3") (pin "1") (pinfunction "1_1") (pintype "bidirectional"))
    )
    (net (code "10") (name "HUB3_B") (class "Default")
      (node (ref "IC19") (pin "7") (pinfunction "B_7") (pintype "passive"))
      (node (ref "R84") (pin "1") (pinfunction "1_1") (pintype "passive"))
      (node (ref "R85") (pin "2") (pinfunction "2_2") (pintype "passive"))
      (node (ref "TOHUB3") (pin "6") (pinfunction "4_6") (pintype "bidirectional"))
    )
    (net (code "11") (name "HUB4_A") (class "Default")
      (node (ref "IC22") (pin "6") (pinfunction "A_6") (pintype "passive"))
      (node (ref "R92") (pin "2") (pinfunction "2_2") (pintype "passive"))
      (node (ref "TOHUB4") (pin "1") (pinfunction "1_1") (pintype "bidirectional"))
    )
    (net (code "12") (name "HUB4_B") (class "Default")
      (node (ref "IC22") (pin "7") (pinfunction "B_7") (pintype "passive"))
      (node (ref "R93") (pin "1") (pinfunction "1_1") (pintype "passive"))
      (node (ref "R94") (pin "2") (pinfunction "2_2") (pintype "passive"))
      (node (ref "TOHUB4") (pin "6") (pinfunction "4_6") (pintype "bidirectional"))
    )
    (net (code "13") (name "HUB5_A") (class "Default")
      (node (ref "IC23") (pin "6") (pinfunction "A_6") (pintype "passive"))
      (node (ref "R101") (pin "2") (pinfunction "2_2") (pintype "passive"))
      (node (ref "TOHUB5") (pin "1") (pinfunction "1_1") (pintype "bidirectional"))
    )
    (net (code "14") (name "HUB5_B") (class "Default")
      (node (ref "IC23") (pin "7") (pinfunction "B_7") (pintype "passive"))
      (node (ref "R102") (pin "1") (pinfunction "1_1") (pintype "passive"))
      (node (ref "R103") (pin "2") (pinfunction "2_2") (pintype "passive"))
      (node (ref "TOHUB5") (pin "6") (pinfunction "4_6") (pintype "bidirectional"))
    )
    (net (code "15") (name "HUB6_A") (class "Default")
      (node (ref "IC24") (pin "6") (pinfunction "A_6") (pintype "passive"))
      (node (ref "R111") (pin "2") (pinfunction "2_2") (pintype "passive"))
      (node (ref "TOHUB6") (pin "1") (pinfunction "1_1") (pintype "bidirectional"))
    )
    (net (code "16") (name "HUB6_B") (class "Default")
      (node (ref "IC24") (pin "7") (pinfunction "B_7") (pintype "passive"))
      (node (ref "R112") (pin "1") (pinfunction "1_1") (pintype "passive"))
      (node (ref "R113") (pin "2") (pinfunction "2_2") (pintype "passive"))
      (node (ref "TOHUB6") (pin "6") (pinfunction "4_6") (pintype "bidirectional"))
    )
    (net (code "17") (name "IN1_DATA1+") (class "Default")
      (node (ref "DMX1") (pin "3") (pinfunction "3_3") (pintype "passive"))
      (node (ref "FLIP1") (pin "5") (pinfunction "5_5") (pintype "bidirectional"))
    )
    (net (code "18") (name "IN1_DATA1-") (class "Default")
      (node (ref "DMX1") (pin "2") (pinfunction "2_2") (pintype "passive"))
      (node (ref "FLIP1") (pin "2") (pinfunction "2_2") (pintype "bidirectional"))
    )
    (net (code "19") (name "IN2_DATA+") (class "Default")
      (node (ref "DMX2") (pin "3") (pinfunction "3_3") (pintype "passive"))
      (node (ref "FLIP2") (pin "2") (pinfunction "2_2") (pintype "bidirectional"))
    )
    (net (code "20") (name "IN2_DATA-") (class "Default")
      (node (ref "DMX2") (pin "2") (pinfunction "1_2") (pintype "passive"))
      (node (ref "FLIP2") (pin "5") (pinfunction "5_5") (pintype "bidirectional"))
    )
    (net (code "21") (name "IN3_DATA1+") (class "Default")
      (node (ref "DMX3") (pin "3") (pinfunction "3_3") (pintype "passive"))
      (node (ref "FLIP3") (pin "2") (pinfunction "2_2") (pintype "bidirectional"))
    )
    (net (code "22") (name "IN3_DATA1-") (class "Default")
      (node (ref "DMX3") (pin "2") (pinfunction "2_2") (pintype "passive"))
      (node (ref "FLIP3") (pin "5") (pinfunction "5_5") (pintype "bidirectional"))
    )
    (net (code "23") (name "IN3_DATA2+") (class "Default")
      (node (ref "DMX3") (pin "5") (pinfunction "5_5") (pintype "passive"))
      (node (ref "JP15") (pin "2") (pinfunction "2_2") (pintype "passive"))
    )
    (net (code "24") (name "IN3_DATA2-") (class "Default")
      (node (ref "DMX3") (pin "4") (pinfunction "4_4") (pintype "passive"))
      (node (ref "JP15") (pin "1") (pinfunction "1_1") (pintype "passive"))
    )
    (net (code "25") (name "IN4_DATA1+") (class "Default")
      (node (ref "DMX4") (pin "3") (pinfunction "3_3") (pintype "passive"))
      (node (ref "FLIP4") (pin "2") (pinfunction "2_2") (pintype "bidirectional"))
    )
    (net (code "26") (name "IN4_DATA1-") (class "Default")
      (node (ref "DMX4") (pin "2") (pinfunction "2_2") (pintype "passive"))
      (node (ref "FLIP4") (pin "5") (pinfunction "5_5") (pintype "bidirectional"))
    )
    (net (code "27") (name "IN4_DATA2+") (class "Default")
      (node (ref "DMX4") (pin "5") (pinfunction "5_5") (pintype "passive"))
      (node (ref "JP16") (pin "2") (pinfunction "2_2") (pintype "passive"))
    )
    (net (code "28") (name "IN4_DATA2-") (class "Default")
      (node (ref "DMX4") (pin "4") (pinfunction "4_4") (pintype "passive"))
      (node (ref "JP16") (pin "1") (pinfunction "1_1") (pintype "passive"))
    )
    (net (code "29") (name "IN5_DATA1+") (class "Default")
      (node (ref "DMX5") (pin "P1") (pinfunction "P$1_P1") (pintype "bidirectional"))
      (node (ref "FLIP5") (pin "5") (pinfunction "5_5") (pintype "bidirectional"))
    )
    (net (code "30") (name "IN5_DATA1-") (class "Default")
      (node (ref "DMX5") (pin "P2") (pinfunction "P$2_P2") (pintype "bidirectional"))
      (node (ref "FLIP5") (pin "2") (pinfunction "2_2") (pintype "bidirectional"))
    )
    (net (code "31") (name "IN5_DATA2+") (class "Default")
      (node (ref "DMX5") (pin "P3") (pinfunction "P$3_P3") (pintype "bidirectional"))
      (node (ref "JP13") (pin "1") (pinfunction "1_1") (pintype "passive"))
    )
    (net (code "32") (name "IN5_DATA2-") (class "Default")
      (node (ref "DMX5") (pin "P6") (pinfunction "P$6_P6") (pintype "bidirectional"))
      (node (ref "JP13") (pin "2") (pinfunction "2_2") (pintype "passive"))
    )
    (net (code "33") (name "IN6_DATA1+") (class "Default")
      (node (ref "DMX6") (pin "P1") (pinfunction "P$1_P1") (pintype "bidirectional"))
      (node (ref "FLIP6") (pin "5") (pinfunction "5_5") (pintype "bidirectional"))
    )
    (net (code "34") (name "IN6_DATA1-") (class "Default")
      (node (ref "DMX6") (pin "P2") (pinfunction "P$2_P2") (pintype "bidirectional"))
      (node (ref "FLIP6") (pin "2") (pinfunction "2_2") (pintype "bidirectional"))
    )
    (net (code "35") (name "IN6_DATA2+") (class "Default")
      (node (ref "DMX6") (pin "P3") (pinfunction "P$3_P3") (pintype "bidirectional"))
      (node (ref "JP14") (pin "1") (pinfunction "1_1") (pintype "passive"))
    )
    (net (code "36") (name "IN6_DATA2-") (class "Default")
      (node (ref "DMX6") (pin "P6") (pinfunction "P$6_P6") (pintype "bidirectional"))
      (node (ref "JP14") (pin "2") (pinfunction "2_2") (pintype "passive"))
    )
    (net (code "37") (name "Net-(C2-Pad1)") (class "Default")
      (node (ref "C2") (pin "1") (pinfunction "1_1") (pintype "passive"))
      (node (ref "IC1") (pin "2") (pinfunction "OUT_2") (pintype "output"))
      (node (ref "IC1") (pin "4") (pinfunction "OUT_4") (pintype "output"))
      (node (ref "POWER") (pin "1") (pinfunction "1_1") (pintype "bidirectional"))
    )
    (net (code "38") (name "Net-(C17-Pad1)") (class "Default")
      (node (ref "C17") (pin "1") (pinfunction "1_1") (pintype "passive"))
      (node (ref "R52") (pin "1") (pinfunction "1_1") (pintype "passive"))
    )
    (net (code "39") (name "Net-(C18-Pad1)") (class "Default")
      (node (ref "C18") (pin "1") (pinfunction "1_1") (pintype "passive"))
      (node (ref "R71") (pin "1") (pinfunction "1_1") (pintype "passive"))
    )
    (net (code "40") (name "Net-(C19-Pad1)") (class "Default")
      (node (ref "C19") (pin "1") (pinfunction "1_1") (pintype "passive"))
      (node (ref "R81") (pin "1") (pinfunction "1_1") (pintype "passive"))
    )
    (net (code "41") (name "Net-(C20-Pad1)") (class "Default")
      (node (ref "C20") (pin "1") (pinfunction "1_1") (pintype "passive"))
      (node (ref "R90") (pin "1") (pinfunction "1_1") (pintype "passive"))
    )
    (net (code "42") (name "Net-(C21-Pad1)") (class "Default")
      (node (ref "C21") (pin "1") (pinfunction "1_1") (pintype "passive"))
      (node (ref "R99") (pin "1") (pinfunction "1_1") (pintype "passive"))
    )
    (net (code "43") (name "Net-(C22-Pad1)") (class "Default")
      (node (ref "C22") (pin "1") (pinfunction "1_1") (pintype "passive"))
      (node (ref "R109") (pin "1") (pinfunction "1_1") (pintype "passive"))
    )
    (net (code "44") (name "Net-(DMX5B-PA$1)") (class "Default")
      (node (ref "DMX5") (pin "P1A") (pinfunction "PA$1_P1A") (pintype "bidirectional"))
      (node (ref "R97") (pin "1") (pinfunction "1_1") (pintype "passive"))
    )
    (net (code "45") (name "Net-(DMX5C-PA$1)") (class "Default")
      (node (ref "DMX5") (pin "P2A") (pinfunction "PA$1_P2A") (pintype "bidirectional"))
      (node (ref "R98") (pin "1") (pinfunction "1_1") (pintype "passive"))
    )
    (net (code "46") (name "Net-(DMX6B-PA$1)") (class "Default")
      (node (ref "DMX6") (pin "P1A") (pinfunction "PA$1_P1A") (pintype "bidirectional"))
      (node (ref "R107") (pin "1") (pinfunction "1_1") (pintype "passive"))
    )
    (net (code "47") (name "Net-(DMX6C-PA$1)") (class "Default")
      (node (ref "DMX6") (pin "P2A") (pinfunction "PA$1_P2A") (pintype "bidirectional"))
      (node (ref "R108") (pin "1") (pinfunction "1_1") (pintype "passive"))
    )
    (net (code "48") (name "Net-(FLIP1-4)") (class "Default")
      (node (ref "FLIP1") (pin "3") (pinfunction "3_3") (pintype "bidirectional"))
      (node (ref "FLIP1") (pin "6") (pinfunction "4_6") (pintype "bidirectional"))
      (node (ref "TOHUB1") (pin "2") (pinfunction "2_2") (pintype "bidirectional"))
    )
    (net (code "49") (name "Net-(FLIP1-6)") (class "Default")
      (node (ref "FLIP1") (pin "1") (pinfunction "1_1") (pintype "bidirectional"))
      (node (ref "FLIP1") (pin "4") (pinfunction "6_4") (pintype "bidirectional"))
      (node (ref "TOHUB1") (pin "5") (pinfunction "5_5") (pintype "bidirectional"))
    )
    (net (code "50") (name "Net-(FLIP2-4)") (class "Default")
      (node (ref "FLIP2") (pin "3") (pinfunction "3_3") (pintype "bidirectional"))
      (node (ref "FLIP2") (pin "6") (pinfunction "4_6") (pintype "bidirectional"))
      (node (ref "TOHUB2") (pin "2") (pinfunction "2_2") (pintype "bidirectional"))
    )
    (net (code "51") (name "Net-(FLIP2-6)") (class "Default")
      (node (ref "FLIP2") (pin "1") (pinfunction "1_1") (pintype "bidirectional"))
      (node (ref "FLIP2") (pin "4") (pinfunction "6_4") (pintype "bidirectional"))
      (node (ref "TOHUB2") (pin "5") (pinfunction "5_5") (pintype "bidirectional"))
    )
    (net (code "52") (name "Net-(FLIP3-4)") (class "Default")
      (node (ref "FLIP3") (pin "3") (pinfunction "3_3") (pintype "bidirectional"))
      (node (ref "FLIP3") (pin "6") (pinfunction "4_6") (pintype "bidirectional"))
      (node (ref "TOHUB3") (pin "2") (pinfunction "2_2") (pintype "bidirectional"))
    )
    (net (code "53") (name "Net-(FLIP3-6)") (class "Default")
      (node (ref "FLIP3") (pin "1") (pinfunction "1_1") (pintype "bidirectional"))
      (node (ref "FLIP3") (pin "4") (pinfunction "6_4") (pintype "bidirectional"))
      (node (ref "TOHUB3") (pin "5") (pinfunction "5_5") (pintype "bidirectional"))
    )
    (net (code "54") (name "Net-(FLIP4-4)") (class "Default")
      (node (ref "FLIP4") (pin "3") (pinfunction "3_3") (pintype "bidirectional"))
      (node (ref "FLIP4") (pin "6") (pinfunction "4_6") (pintype "bidirectional"))
      (node (ref "TOHUB4") (pin "2") (pinfunction "2_2") (pintype "bidirectional"))
    )
    (net (code "55") (name "Net-(FLIP4-6)") (class "Default")
      (node (ref "FLIP4") (pin "1") (pinfunction "1_1") (pintype "bidirectional"))
      (node (ref "FLIP4") (pin "4") (pinfunction "6_4") (pintype "bidirectional"))
      (node (ref "TOHUB4") (pin "5") (pinfunction "5_5") (pintype "bidirectional"))
    )
    (net (code "56") (name "Net-(FLIP5-4)") (class "Default")
      (node (ref "FLIP5") (pin "3") (pinfunction "3_3") (pintype "bidirectional"))
      (node (ref "FLIP5") (pin "6") (pinfunction "4_6") (pintype "bidirectional"))
      (node (ref "TOHUB5") (pin "2") (pinfunction "2_2") (pintype "bidirectional"))
    )
    (net (code "57") (name "Net-(FLIP5-6)") (class "Default")
      (node (ref "FLIP5") (pin "1") (pinfunction "1_1") (pintype "bidirectional"))
      (node (ref "FLIP5") (pin "4") (pinfunction "6_4") (pintype "bidirectional"))
      (node (ref "TOHUB5") (pin "5") (pinfunction "5_5") (pintype "bidirectional"))
    )
    (net (code "58") (name "Net-(FLIP6-4)") (class "Default")
      (node (ref "FLIP6") (pin "3") (pinfunction "3_3") (pintype "bidirectional"))
      (node (ref "FLIP6") (pin "6") (pinfunction "4_6") (pintype "bidirectional"))
      (node (ref "TOHUB6") (pin "2") (pinfunction "2_2") (pintype "bidirectional"))
    )
    (net (code "59") (name "Net-(FLIP6-6)") (class "Default")
      (node (ref "FLIP6") (pin "1") (pinfunction "1_1") (pintype "bidirectional"))
      (node (ref "FLIP6") (pin "4") (pinfunction "6_4") (pintype "bidirectional"))
      (node (ref "TOHUB6") (pin "5") (pinfunction "5_5") (pintype "bidirectional"))
    )
    (net (code "60") (name "Net-(IC11A-O)") (class "Default")
      (node (ref "IC11") (pin "12") (pinfunction "I0_12") (pintype "input"))
      (node (ref "IC11") (pin "3") (pinfunction "O_3") (pintype "output"))
    )
    (net (code "61") (name "Net-(IC11B-I0)") (class "Default")
      (node (ref "D19") (pin "C") (pinfunction "C_C") (pintype "passive"))
      (node (ref "IC11") (pin "13") (pinfunction "I1_13") (pintype "input"))
      (node (ref "IC11") (pin "4") (pinfunction "I0_4") (pintype "input"))
      (node (ref "IC11") (pin "5") (pinfunction "I1_5") (pintype "input"))
      (node (ref "IC21") (pin "1") (pinfunction "RO_1") (pintype "output"))
      (node (ref "R10") (pin "1") (pinfunction "1_1") (pintype "passive"))
    )
    (net (code "62") (name "Net-(IC11B-O)") (class "Default")
      (node (ref "IC11") (pin "6") (pinfunction "O_6") (pintype "output"))
      (node (ref "R30") (pin "2") (pinfunction "2_2") (pintype "passive"))
    )
    (net (code "63") (name "Net-(IC11C-I0)") (class "Default")
      (node (ref "D24") (pin "A") (pinfunction "A_A") (pintype "passive"))
      (node (ref "IC11") (pin "10") (pinfunction "I1_10") (pintype "input"))
      (node (ref "IC11") (pin "9") (pinfunction "I0_9") (pintype "input"))
      (node (ref "R52") (pin "2") (pinfunction "2_2") (pintype "passive"))
      (node (ref "R63") (pin "1") (pinfunction "1_1") (pintype "passive"))
    )
    (net (code "64") (name "Net-(IC11D-O)") (class "Default")
      (node (ref "D24") (pin "C") (pinfunction "C_C") (pintype "passive"))
      (node (ref "IC11") (pin "11") (pinfunction "O_11") (pintype "output"))
      (node (ref "IC21") (pin "4") (pinfunction "DI_4") (pintype "input"))
      (node (ref "R63") (pin "2") (pinfunction "2_2") (pintype "passive"))
    )
    (net (code "65") (name "Net-(IC14A-O)") (class "Default")
      (node (ref "IC14") (pin "12") (pinfunction "I0_12") (pintype "input"))
      (node (ref "IC14") (pin "3") (pinfunction "O_3") (pintype "output"))
    )
    (net (code "66") (name "Net-(IC14B-I0)") (class "Default")
      (node (ref "D20") (pin "C") (pinfunction "C_C") (pintype "passive"))
      (node (ref "IC14") (pin "13") (pinfunction "I1_13") (pintype "input"))
      (node (ref "IC14") (pin "4") (pinfunction "I0_4") (pintype "input"))
      (node (ref "IC14") (pin "5") (pinfunction "I1_5") (pintype "input"))
      (node (ref "IC20") (pin "1") (pinfunction "RO_1") (pintype "output"))
      (node (ref "R67") (pin "1") (pinfunction "1_1") (pintype "passive"))
    )
    (net (code "67") (name "Net-(IC14B-O)") (class "Default")
      (node (ref "IC14") (pin "6") (pinfunction "O_6") (pintype "output"))
      (node (ref "R69") (pin "2") (pinfunction "2_2") (pintype "passive"))
    )
    (net (code "68") (name "Net-(IC14C-I0)") (class "Default")
      (node (ref "D23") (pin "A") (pinfunction "A_A") (pintype "passive"))
      (node (ref "IC14") (pin "10") (pinfunction "I1_10") (pintype "input"))
      (node (ref "IC14") (pin "9") (pinfunction "I0_9") (pintype "input"))
      (node (ref "R71") (pin "2") (pinfunction "2_2") (pintype "passive"))
      (node (ref "R72") (pin "1") (pinfunction "1_1") (pintype "passive"))
    )
    (net (code "69") (name "Net-(IC14D-O)") (class "Default")
      (node (ref "D23") (pin "C") (pinfunction "C_C") (pintype "passive"))
      (node (ref "IC14") (pin "11") (pinfunction "O_11") (pintype "output"))
      (node (ref "IC20") (pin "4") (pinfunction "DI_4") (pintype "input"))
      (node (ref "R72") (pin "2") (pinfunction "2_2") (pintype "passive"))
    )
    (net (code "70") (name "Net-(IC15A-O)") (class "Default")
      (node (ref "IC15") (pin "12") (pinfunction "I0_12") (pintype "input"))
      (node (ref "IC15") (pin "3") (pinfunction "O_3") (pintype "output"))
    )
    (net (code "71") (name "Net-(IC15B-I0)") (class "Default")
      (node (ref "D21") (pin "C") (pinfunction "C_C") (pintype "passive"))
      (node (ref "IC15") (pin "13") (pinfunction "I1_13") (pintype "input"))
      (node (ref "IC15") (pin "4") (pinfunction "I0_4") (pintype "input"))
      (node (ref "IC15") (pin "5") (pinfunction "I1_5") (pintype "input"))
      (node (ref "IC19") (pin "1") (pinfunction "RO_1") (pintype "output"))
      (node (ref "R77") (pin "1") (pinfunction "1_1") (pintype "passive"))
    )
    (net (code "72") (name "Net-(IC15B-O)") (class "Default")
      (node (ref "IC15") (pin "6") (pinfunction "O_6") (pintype "output"))
      (node (ref "R79") (pin "2") (pinfunction "2_2") (pintype "passive"))
    )
    (net (code "73") (name "Net-(IC15C-I0)") (class "Default")
      (node (ref "D22") (pin "A") (pinfunction "A_A") (pintype "passive"))
      (node (ref "IC15") (pin "10") (pinfunction "I1_10") (pintype "input"))
      (node (ref "IC15") (pin "9") (pinfunction "I0_9") (pintype "input"))
      (node (ref "R81") (pin "2") (pinfunction "2_2") (pintype "passive"))
      (node (ref "R82") (pin "1") (pinfunction "1_1") (pintype "passive"))
    )
    (net (code "74") (name "Net-(IC15D-O)") (class "Default")
      (node (ref "D22") (pin "C") (pinfunction "C_C") (pintype "passive"))
      (node (ref "IC15") (pin "11") (pinfunction "O_11") (pintype "output"))
      (node (ref "IC19") (pin "4") (pinfunction "DI_4") (pintype "input"))
      (node (ref "R82") (pin "2") (pinfunction "2_2") (pintype "passive"))
    )
    (net (code "75") (name "Net-(IC16A-O)") (class "Default")
      (node (ref "IC16") (pin "12") (pinfunction "I0_12") (pintype "input"))
      (node (ref "IC16") (pin "3") (pinfunction "O_3") (pintype "output"))
    )
    (net (code "76") (name "Net-(IC16B-I0)") (class "Default")
      (node (ref "D14") (pin "C") (pinfunction "C_C") (pintype "passive"))
      (node (ref "IC16") (pin "13") (pinfunction "I1_13") (pintype "input"))
      (node (ref "IC16") (pin "4") (pinfunction "I0_4") (pintype "input"))
      (node (ref "IC16") (pin "5") (pinfunction "I1_5") (pintype "input"))
      (node (ref "IC22") (pin "1") (pinfunction "RO_1") (pintype "output"))
      (node (ref "R86") (pin "1") (pinfunction "1_1") (pintype "passive"))
    )
    (net (code "77") (name "Net-(IC16B-O)") (class "Default")
      (node (ref "IC16") (pin "6") (pinfunction "O_6") (pintype "output"))
      (node (ref "R88") (pin "2") (pinfunction "2_2") (pintype "passive"))
    )
    (net (code "78") (name "Net-(IC16C-I0)") (class "Default")
      (node (ref "D12") (pin "A") (pinfunction "A_A") (pintype "passive"))
      (node (ref "IC16") (pin "10") (pinfunction "I1_10") (pintype "input"))
      (node (ref "IC16") (pin "9") (pinfunction "I0_9") (pintype "input"))
      (node (ref "R90") (pin "2") (pinfunction "2_2") (pintype "passive"))
      (node (ref "R91") (pin "1") (pinfunction "1_1") (pintype "passive"))
    )
    (net (code "79") (name "Net-(IC16D-O)") (class "Default")
      (node (ref "D12") (pin "C") (pinfunction "C_C") (pintype "passive"))
      (node (ref "IC16") (pin "11") (pinfunction "O_11") (pintype "output"))
      (node (ref "IC22") (pin "4") (pinfunction "DI_4") (pintype "input"))
      (node (ref "R91") (pin "2") (pinfunction "2_2") (pintype "passive"))
    )
    (net (code "80") (name "Net-(IC17A-O)") (class "Default")
      (node (ref "IC17") (pin "12") (pinfunction "I0_12") (pintype "input"))
      (node (ref "IC17") (pin "3") (pinfunction "O_3") (pintype "output"))
    )
    (net (code "81") (name "Net-(IC17B-I0)") (class "Default")
      (node (ref "D15") (pin "C") (pinfunction "C_C") (pintype "passive"))
      (node (ref "IC17") (pin "13") (pinfunction "I1_13") (pintype "input"))
      (node (ref "IC17") (pin "4") (pinfunction "I0_4") (pintype "input"))
      (node (ref "IC17") (pin "5") (pinfunction "I1_5") (pintype "input"))
      (node (ref "IC23") (pin "1") (pinfunction "RO_1") (pintype "output"))
      (node (ref "R95") (pin "1") (pinfunction "1_1") (pintype "passive"))
    )
    (net (code "82") (name "Net-(IC17B-O)") (class "Default")
      (node (ref "IC17") (pin "6") (pinfunction "O_6") (pintype "output"))
      (node (ref "R97") (pin "2") (pinfunction "2_2") (pintype "passive"))
    )
    (net (code "83") (name "Net-(IC17C-I0)") (class "Default")
      (node (ref "D16") (pin "A") (pinfunction "A_A") (pintype "passive"))
      (node (ref "IC17") (pin "10") (pinfunction "I1_10") (pintype "input"))
      (node (ref "IC17") (pin "9") (pinfunction "I0_9") (pintype "input"))
      (node (ref "R100") (pin "1") (pinfunction "1_1") (pintype "passive"))
      (node (ref "R99") (pin "2") (pinfunction "2_2") (pintype "passive"))
    )
    (net (code "84") (name "Net-(IC17D-O)") (class "Default")
      (node (ref "D16") (pin "C") (pinfunction "C_C") (pintype "passive"))
      (node (ref "IC17") (pin "11") (pinfunction "O_11") (pintype "output"))
      (node (ref "IC23") (pin "4") (pinfunction "DI_4") (pintype "input"))
      (node (ref "R100") (pin "2") (pinfunction "2_2") (pintype "passive"))
    )
    (net (code "85") (name "Net-(IC18A-O)") (class "Default")
      (node (ref "IC18") (pin "12") (pinfunction "I0_12") (pintype "input"))
      (node (ref "IC18") (pin "3") (pinfunction "O_3") (pintype "output"))
    )
    (net (code "86") (name "Net-(IC18B-I0)") (class "Default")
      (node (ref "D17") (pin "C") (pinfunction "C_C") (pintype "passive"))
      (node (ref "IC18") (pin "13") (pinfunction "I1_13") (pintype "input"))
      (node (ref "IC18") (pin "4") (pinfunction "I0_4") (pintype "input"))
      (node (ref "IC18") (pin "5") (pinfunction "I1_5") (pintype "input"))
      (node (ref "IC24") (pin "1") (pinfunction "RO_1") (pintype "output"))
      (node (ref "R105") (pin "1") (pinfunction "1_1") (pintype "passive"))
    )
    (net (code "87") (name "Net-(IC18B-O)") (class "Default")
      (node (ref "IC18") (pin "6") (pinfunction "O_6") (pintype "output"))
      (node (ref "R107") (pin "2") (pinfunction "2_2") (pintype "passive"))
    )
    (net (code "88") (name "Net-(IC18C-I0)") (class "Default")
      (node (ref "D18") (pin "A") (pinfunction "A_A") (pintype "passive"))
      (node (ref "IC18") (pin "10") (pinfunction "I1_10") (pintype "input"))
      (node (ref "IC18") (pin "9") (pinfunction "I0_9") (pintype "input"))
      (node (ref "R109") (pin "2") (pinfunction "2_2") (pintype "passive"))
      (node (ref "R110") (pin "1") (pinfunction "1_1") (pintype "passive"))
    )
    (net (code "89") (name "Net-(IC18D-O)") (class "Default")
      (node (ref "D18") (pin "C") (pinfunction "C_C") (pintype "passive"))
      (node (ref "IC18") (pin "11") (pinfunction "O_11") (pintype "output"))
      (node (ref "IC24") (pin "4") (pinfunction "DI_4") (pintype "input"))
      (node (ref "R110") (pin "2") (pinfunction "2_2") (pintype "passive"))
    )
    (net (code "90") (name "Net-(LD2-PadA)") (class "Default")
      (node (ref "LD2") (pin "A") (pinfunction "A_A") (pintype "passive"))
      (node (ref "R1") (pin "1") (pinfunction "1_1") (pintype "passive"))
    )
    (net (code "91") (name "Net-(LD10-PadA)") (class "Default")
      (node (ref "LD10") (pin "A") (pinfunction "A_A") (pintype "passive"))
      (node (ref "R88") (pin "1") (pinfunction "1_1") (pintype "passive"))
    )
    (net (code "92") (name "Net-(LD11-PadA)") (class "Default")
      (node (ref "LD11") (pin "A") (pinfunction "A_A") (pintype "passive"))
      (node (ref "R89") (pin "1") (pinfunction "1_1") (pintype "passive"))
    )
    (net (code "93") (name "Net-(LD12-PadA)") (class "Default")
      (node (ref "LD12") (pin "A") (pinfunction "A_A") (pintype "passive"))
      (node (ref "R30") (pin "1") (pinfunction "1_1") (pintype "passive"))
    )
    (net (code "94") (name "Net-(LD13-PadA)") (class "Default")
      (node (ref "LD13") (pin "A") (pinfunction "A_A") (pintype "passive"))
      (node (ref "R40") (pin "1") (pinfunction "1_1") (pintype "passive"))
    )
    (net (code "95") (name "Net-(LD14-PadA)") (class "Default")
      (node (ref "LD14") (pin "A") (pinfunction "A_A") (pintype "passive"))
      (node (ref "R69") (pin "1") (pinfunction "1_1") (pintype "passive"))
    )
    (net (code "96") (name "Net-(LD15-PadA)") (class "Default")
      (node (ref "LD15") (pin "A") (pinfunction "A_A") (pintype "passive"))
      (node (ref "R70") (pin "1") (pinfunction "1_1") (pintype "passive"))
    )
    (net (code "97") (name "Net-(LD16-PadA)") (class "Default")
      (node (ref "LD16") (pin "A") (pinfunction "A_A") (pintype "passive"))
      (node (ref "R79") (pin "1") (pinfunction "1_1") (pintype "passive"))
    )
    (net (code "98") (name "Net-(LD17-PadA)") (class "Default")
      (node (ref "LD17") (pin "A") (pinfunction "A_A") (pintype "passive"))
      (node (ref "R80") (pin "1") (pinfunction "1_1") (pintype "passive"))
    )
    (net (code "99") (name "Net-(POWER-4)") (class "Default")
      (node (ref "POWER") (pin "6") (pinfunction "4_6") (pintype "bidirectional"))
      (node (ref "X2") (pin "2") (pinfunction "S_2") (pintype "passive"))
    )
    (net (code "100") (name "Net-(POWER-Pad3)") (class "Default")
      (node (ref "POWER") (pin "3") (pinfunction "3_3") (pintype "bidirectional"))
      (node (ref "X1") (pin "1") (pinfunction "1_1") (pintype "passive"))
    )
    (net (code "101") (name "RXEN_1A") (class "Default")
      (node (ref "IC21") (pin "2") (pinfunction "RE/_2") (pintype "input"))
      (node (ref "R20") (pin "1") (pinfunction "1_1") (pintype "passive"))
      (node (ref "S13") (pin "19") (pinfunction "19_19") (pintype "passive"))
    )
    (net (code "102") (name "RXEN_1B") (class "Default")
      (node (ref "IC11") (pin "8") (pinfunction "O_8") (pintype "output"))
      (node (ref "IC21") (pin "3") (pinfunction "DE_3") (pintype "input"))
      (node (ref "R40") (pin "2") (pinfunction "2_2") (pintype "passive"))
      (node (ref "S13") (pin "2") (pinfunction "2_2") (pintype "passive"))
    )
    (net (code "103") (name "RXEN_2A") (class "Default")
      (node (ref "IC20") (pin "2") (pinfunction "RE/_2") (pintype "input"))
      (node (ref "R68") (pin "1") (pinfunction "1_1") (pintype "passive"))
      (node (ref "S13") (pin "17") (pinfunction "17_17") (pintype "passive"))
    )
    (net (code "104") (name "RXEN_2B") (class "Default")
      (node (ref "IC14") (pin "8") (pinfunction "O_8") (pintype "output"))
      (node (ref "IC20") (pin "3") (pinfunction "DE_3") (pintype "input"))
      (node (ref "R70") (pin "2") (pinfunction "2_2") (pintype "passive"))
      (node (ref "S13") (pin "4") (pinfunction "4_4") (pintype "passive"))
    )
    (net (code "105") (name "RXEN_3A") (class "Default")
      (node (ref "IC19") (pin "2") (pinfunction "RE/_2") (pintype "input"))
      (node (ref "R78") (pin "1") (pinfunction "1_1") (pintype "passive"))
      (node (ref "S13") (pin "15") (pinfunction "15_15") (pintype "passive"))
    )
    (net (code "106") (name "RXEN_3B") (class "Default")
      (node (ref "IC15") (pin "8") (pinfunction "O_8") (pintype "output"))
      (node (ref "IC19") (pin "3") (pinfunction "DE_3") (pintype "input"))
      (node (ref "R80") (pin "2") (pinfunction "2_2") (pintype "passive"))
      (node (ref "S13") (pin "6") (pinfunction "6_6") (pintype "passive"))
    )
    (net (code "107") (name "RXEN_4A") (class "Default")
      (node (ref "IC22") (pin "2") (pinfunction "RE/_2") (pintype "input"))
      (node (ref "R87") (pin "1") (pinfunction "1_1") (pintype "passive"))
      (node (ref "S13") (pin "13") (pinfunction "13_13") (pintype "passive"))
    )
    (net (code "108") (name "RXEN_4B") (class "Default")
      (node (ref "IC16") (pin "8") (pinfunction "O_8") (pintype "output"))
      (node (ref "IC22") (pin "3") (pinfunction "DE_3") (pintype "input"))
      (node (ref "R89") (pin "2") (pinfunction "2_2") (pintype "passive"))
      (node (ref "S13") (pin "8") (pinfunction "8_8") (pintype "passive"))
    )
    (net (code "109") (name "RXEN_5A") (class "Default")
      (node (ref "IC23") (pin "2") (pinfunction "RE/_2") (pintype "input"))
      (node (ref "R96") (pin "1") (pinfunction "1_1") (pintype "passive"))
      (node (ref "S13") (pin "11") (pinfunction "11_11") (pintype "passive"))
    )
    (net (code "110") (name "RXEN_5B") (class "Default")
      (node (ref "IC17") (pin "8") (pinfunction "O_8") (pintype "output"))
      (node (ref "IC23") (pin "3") (pinfunction "DE_3") (pintype "input"))
      (node (ref "R98") (pin "2") (pinfunction "2_2") (pintype "passive"))
      (node (ref "S13") (pin "10") (pinfunction "10_10") (pintype "passive"))
    )
    (net (code "111") (name "RXEN_6A") (class "Default")
      (node (ref "IC24") (pin "2") (pinfunction "RE/_2") (pintype "input"))
      (node (ref "R106") (pin "1") (pinfunction "1_1") (pintype "passive"))
      (node (ref "S14") (pin "3") (pinfunction "3_3") (pintype "passive"))
    )
    (net (code "112") (name "RXEN_6B") (class "Default")
      (node (ref "IC18") (pin "8") (pinfunction "O_8") (pintype "output"))
      (node (ref "IC24") (pin "3") (pinfunction "DE_3") (pintype "input"))
      (node (ref "R108") (pin "2") (pinfunction "2_2") (pintype "passive"))
      (node (ref "S14") (pin "2") (pinfunction "2_2") (pintype "passive"))
    )
    (net (code "113") (name "TERM_1") (class "Default")
      (node (ref "R66") (pin "1") (pinfunction "1_1") (pintype "passive"))
      (node (ref "S13") (pin "20") (pinfunction "20_20") (pintype "passive"))
    )
    (net (code "114") (name "TERM_2") (class "Default")
      (node (ref "R75") (pin "1") (pinfunction "1_1") (pintype "passive"))
      (node (ref "S13") (pin "18") (pinfunction "18_18") (pintype "passive"))
    )
    (net (code "115") (name "TERM_3") (class "Default")
      (node (ref "R85") (pin "1") (pinfunction "1_1") (pintype "passive"))
      (node (ref "S13") (pin "16") (pinfunction "16_16") (pintype "passive"))
    )
    (net (code "116") (name "TERM_4") (class "Default")
      (node (ref "R94") (pin "1") (pinfunction "1_1") (pintype "passive"))
      (node (ref "S13") (pin "14") (pinfunction "14_14") (pintype "passive"))
    )
    (net (code "117") (name "TERM_5") (class "Default")
      (node (ref "R103") (pin "1") (pinfunction "1_1") (pintype "passive"))
      (node (ref "S13") (pin "12") (pinfunction "12_12") (pintype "passive"))
    )
    (net (code "118") (name "TERM_6") (class "Default")
      (node (ref "R113") (pin "1") (pinfunction "1_1") (pintype "passive"))
      (node (ref "S14") (pin "4") (pinfunction "4_4") (pintype "passive"))
    )
    (net (code "119") (name "VCC") (class "Default")
      (node (ref "C15") (pin "1") (pinfunction "1_1") (pintype "passive"))
      (node (ref "C16") (pin "1") (pinfunction "1_1") (pintype "passive"))
      (node (ref "C23") (pin "1") (pinfunction "1_1") (pintype "passive"))
      (node (ref "C24") (pin "1") (pinfunction "1_1") (pintype "passive"))
      (node (ref "C25") (pin "1") (pinfunction "1_1") (pintype "passive"))
      (node (ref "C26") (pin "1") (pinfunction "1_1") (pintype "passive"))
      (node (ref "C27") (pin "1") (pinfunction "1_1") (pintype "passive"))
      (node (ref "C28") (pin "1") (pinfunction "1_1") (pintype "passive"))
      (node (ref "C3") (pin "+") (pinfunction "+_+") (pintype "passive"))
      (node (ref "C30") (pin "1") (pinfunction "1_1") (pintype "passive"))
      (node (ref "C31") (pin "1") (pinfunction "1_1") (pintype "passive"))
      (node (ref "C32") (pin "1") (pinfunction "1_1") (pintype "passive"))
      (node (ref "C4") (pin "1") (pinfunction "1_1") (pintype "passive"))
      (node (ref "IC19") (pin "8") (pinfunction "VCC_8") (pintype "power_in"))
      (node (ref "IC20") (pin "8") (pinfunction "VCC_8") (pintype "power_in"))
      (node (ref "IC21") (pin "8") (pinfunction "VCC_8") (pintype "power_in"))
      (node (ref "IC22") (pin "8") (pinfunction "VCC_8") (pintype "power_in"))
      (node (ref "IC23") (pin "8") (pinfunction "VCC_8") (pintype "power_in"))
      (node (ref "IC24") (pin "8") (pinfunction "VCC_8") (pintype "power_in"))
      (node (ref "POWER") (pin "2") (pinfunction "2_2") (pintype "bidirectional"))
      (node (ref "R1") (pin "2") (pinfunction "2_2") (pintype "passive"))
      (node (ref "R10") (pin "2") (pinfunction "2_2") (pintype "passive"))
      (node (ref "R101") (pin "1") (pinfunction "1_1") (pintype "passive"))
      (node (ref "R104") (pin "2") (pinfunction "2_2") (pintype "passive"))
      (node (ref "R105") (pin "2") (pinfunction "2_2") (pintype "passive"))
      (node (ref "R106") (pin "2") (pinfunction "2_2") (pintype "passive"))
      (node (ref "R111") (pin "1") (pinfunction "1_1") (pintype "passive"))
      (node (ref "R20") (pin "2") (pinfunction "2_2") (pintype "passive"))
      (node (ref "R64") (pin "1") (pinfunction "1_1") (pintype "passive"))
      (node (ref "R67") (pin "2") (pinfunction "2_2") (pintype "passive"))
      (node (ref "R68") (pin "2") (pinfunction "2_2") (pintype "passive"))
      (node (ref "R73") (pin "1") (pinfunction "1_1") (pintype "passive"))
      (node (ref "R76") (pin "2") (pinfunction "2_2") (pintype "passive"))
      (node (ref "R77") (pin "2") (pinfunction "2_2") (pintype "passive"))
      (node (ref "R78") (pin "2") (pinfunction "2_2") (pintype "passive"))
      (node (ref "R83") (pin "1") (pinfunction "1_1") (pintype "passive"))
      (node (ref "R86") (pin "2") (pinfunction "2_2") (pintype "passive"))
      (node (ref "R87") (pin "2") (pinfunction "2_2") (pintype "passive"))
      (node (ref "R92") (pin "1") (pinfunction "1_1") (pintype "passive"))
      (node (ref "R95") (pin "2") (pinfunction "2_2") (pintype "passive"))
      (node (ref "R96") (pin "2") (pinfunction "2_2") (pintype "passive"))
      (node (ref "X3") (pin "2") (pinfunction "S_2") (pintype "passive"))
    )
    (net (code "120") (name "VIN") (class "Default")
      (node (ref "C1") (pin "1") (pinfunction "1_1") (pintype "passive"))
      (node (ref "IC1") (pin "3") (pinfunction "IN_3") (pintype "input"))
      (node (ref "POWER") (pin "5") (pinfunction "5_5") (pintype "bidirectional"))
    )
    (net (code "121") (name "unconnected-(DMX5A-P$4-PadP4)") (class "Default")
      (node (ref "DMX5") (pin "P4") (pinfunction "P$4_P4") (pintype "bidirectional"))
    )
    (net (code "122") (name "unconnected-(DMX5A-P$5-PadP5)") (class "Default")
      (node (ref "DMX5") (pin "P5") (pinfunction "P$5_P5") (pintype "bidirectional"))
    )
    (net (code "123") (name "unconnected-(DMX6A-P$4-PadP4)") (class "Default")
      (node (ref "DMX6") (pin "P4") (pinfunction "P$4_P4") (pintype "bidirectional"))
    )
    (net (code "124") (name "unconnected-(DMX6A-P$5-PadP5)") (class "Default")
      (node (ref "DMX6") (pin "P5") (pinfunction "P$5_P5") (pintype "bidirectional"))
    )
    (net (code "125") (name "unconnected-(POWER-6-Pad4)") (class "Default")
      (node (ref "POWER") (pin "4") (pinfunction "6_4") (pintype "bidirectional"))
    )
    (net (code "126") (name "unconnected-(X1-Pad2)") (class "Default")
      (node (ref "X1") (pin "2") (pinfunction "2_2") (pintype "passive"))
    )
    (net (code "127") (name "unconnected-(X1-Pad3)") (class "Default")
      (node (ref "X1") (pin "3") (pinfunction "3_3") (pintype "passive"))
    )
    (net (code "128") (name "unconnected-(X1-PadS1)") (class "Default")
      (node (ref "X1") (pin "S1") (pinfunction "S1_S1") (pintype "passive"))
    )
    (net (code "129") (name "unconnected-(X1-PadS2)") (class "Default")
      (node (ref "X1") (pin "S2") (pinfunction "S2_S2") (pintype "passive"))
    )
  )
)
